# esp32comp.net
KiCad netlist of a schematic drawn in EAGLE
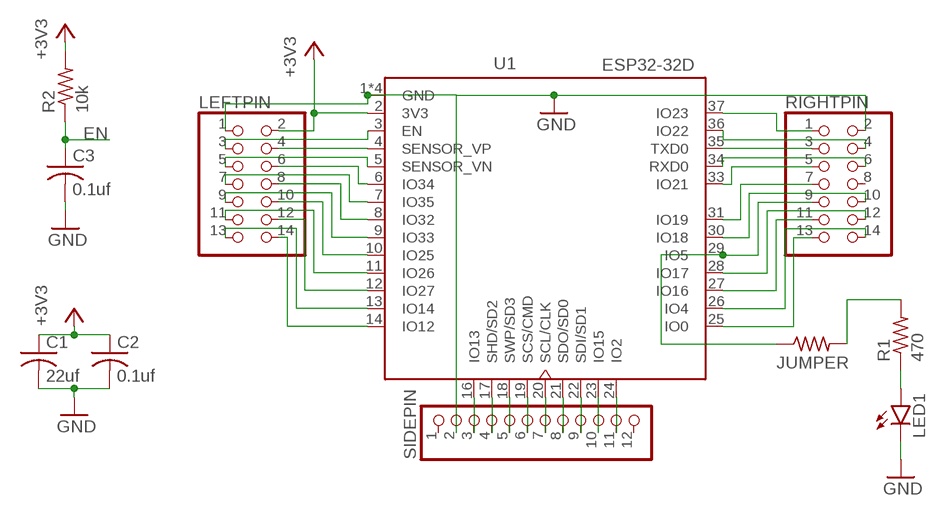
[diagram p0: schematic, sheet 1]

(export (version "E")
  (design (tool "Eeschema 10.0.6"))
  (components
    (comp (ref "C1")
      (value "22uf")
      (footprint "eagle-import:C1210")
      (libsource (lib "eagle-import") (part "C-USC1210"))
    )
    (comp (ref "C2")
      (value "0.1uf")
      (footprint "eagle-import:C0805")
      (libsource (lib "eagle-import") (part "C-USC0805"))
    )
    (comp (ref "C3")
      (value "0.1uf")
      (footprint "eagle-import:C0805")
      (libsource (lib "eagle-import") (part "C-USC0805"))
    )
    (comp (ref "JUMPER")
      (value "RC0603JR-070RL")
      (footprint "eagle-import:RES_0603")
      (fields
        (field (name "DIGIKEY_PART_NUMBER") "311-0.0GRTR-ND")
        (field (name "MANUFACTURER") "Yageo")
        (field (name "CREATED_BY") "PCBLayout.com")
      )
      (libsource (lib "eagle-import") (part "RC0603JR-070RL"))
    )
    (comp (ref "LED1")
      (value "LEDSML0805")
      (footprint "eagle-import:SML0805")
      (libsource (lib "eagle-import") (part "LEDSML0805"))
    )
    (comp (ref "LEFTPIN")
      (value "PINHD-2X7")
      (footprint "eagle-import:2X07")
      (libsource (lib "eagle-import") (part "PINHD-2X7"))
    )
    (comp (ref "R1")
      (value "470")
      (footprint "eagle-import:R0805")
      (libsource (lib "eagle-import") (part "R-US_R0805"))
    )
    (comp (ref "R2")
      (value "10k")
      (footprint "eagle-import:R0805")
      (libsource (lib "eagle-import") (part "R-US_R0805"))
    )
    (comp (ref "RIGHTPIN")
      (value "PINHD-2X7")
      (footprint "eagle-import:2X07")
      (libsource (lib "eagle-import") (part "PINHD-2X7"))
    )
    (comp (ref "SIDEPIN")
      (value "PINHD-1X12")
      (footprint "eagle-import:1X12")
      (libsource (lib "eagle-import") (part "PINHD-1X12"))
    )
    (comp (ref "U1")
      (value "ESP32-32D")
      (footprint "eagle-import:MODULE_ESP32-WROOM-32D")
      (fields (field (name "MF") "Espressif Systems") (field (name "MP") "ESP32-WROOM-32D"))
      (libsource (lib "eagle-import") (part "ESP32-32D"))
    )
  )
  (nets
    (net (code "1") (name "+3V3") (class "Default")
      (node (ref "C1") (pin "1") (pinfunction "1_1") (pintype "passive"))
      (node (ref "C2") (pin "1") (pinfunction "1_1") (pintype "passive"))
      (node (ref "LEFTPIN") (pin "2") (pinfunction "2_2") (pintype "passive"))
      (node (ref "R2") (pin "2") (pinfunction "2_2") (pintype "passive"))
      (node (ref "U1") (pin "2") (pinfunction "3V3_2") (pintype "power_in"))
    )
    (net (code "2") (name "/EN") (class "Default")
      (node (ref "C3") (pin "1") (pinfunction "1_1") (pintype "passive"))
      (node (ref "LEFTPIN") (pin "3") (pinfunction "3_3") (pintype "passive"))
      (node (ref "R2") (pin "1") (pinfunction "1_1") (pintype "passive"))
      (node (ref "U1") (pin "3") (pinfunction "EN_3") (pintype "input"))
    )
    (net (code "3") (name "GND") (class "Default")
      (node (ref "C1") (pin "2") (pinfunction "2_2") (pintype "passive"))
      (node (ref "C2") (pin "2") (pinfunction "2_2") (pintype "passive"))
      (node (ref "C3") (pin "2") (pinfunction "2_2") (pintype "passive"))
      (node (ref "LED1") (pin "C") (pinfunction "C_C") (pintype "passive"))
      (node (ref "LEFTPIN") (pin "1") (pinfunction "1_1") (pintype "passive"))
      (node (ref "RIGHTPIN") (pin "2") (pinfunction "2_2") (pintype "passive"))
      (node (ref "SIDEPIN") (pin "2") (pinfunction "2_2") (pintype "passive"))
      (node (ref "U1") (pin "1") (pinfunction "GND_1") (pintype "power_in"))
      (node (ref "U1") (pin "15") (pinfunction "GND_15") (pintype "power_in"))
      (node (ref "U1") (pin "38") (pinfunction "GND_38") (pintype "power_in"))
      (node (ref "U1") (pin "39") (pinfunction "GND_39") (pintype "power_in"))
    )
    (net (code "4") (name "Net-(JUMPER-Pad2)") (class "Default")
      (node (ref "JUMPER") (pin "2") (pinfunction "2_2") (pintype "passive"))
      (node (ref "R1") (pin "2") (pinfunction "2_2") (pintype "passive"))
    )
    (net (code "5") (name "Net-(LED1-PadA)") (class "Default")
      (node (ref "LED1") (pin "A") (pinfunction "A_A") (pintype "passive"))
      (node (ref "R1") (pin "1") (pinfunction "1_1") (pintype "passive"))
    )
    (net (code "6") (name "Net-(U1-IO0)") (class "Default")
      (node (ref "RIGHTPIN") (pin "13") (pinfunction "13_13") (pintype "passive"))
      (node (ref "U1") (pin "25") (pinfunction "IO0_25") (pintype "bidirectional"))
    )
    (net (code "7") (name "Net-(U1-IO2)") (class "Default")
      (node (ref "SIDEPIN") (pin "11") (pinfunction "11_11") (pintype "passive"))
      (node (ref "U1") (pin "24") (pinfunction "IO2_24") (pintype "bidirectional"))
    )
    (net (code "8") (name "Net-(U1-IO4)") (class "Default")
      (node (ref "RIGHTPIN") (pin "14") (pinfunction "14_14") (pintype "passive"))
      (node (ref "U1") (pin "26") (pinfunction "IO4_26") (pintype "bidirectional"))
    )
    (net (code "9") (name "Net-(U1-IO5)") (class "Default")
      (node (ref "JUMPER") (pin "1") (pinfunction "1_1") (pintype "passive"))
      (node (ref "RIGHTPIN") (pin "9") (pinfunction "9_9") (pintype "passive"))
      (node (ref "U1") (pin "29") (pinfunction "IO5_29") (pintype "bidirectional"))
    )
    (net (code "10") (name "Net-(U1-IO12)") (class "Default")
      (node (ref "LEFTPIN") (pin "14") (pinfunction "14_14") (pintype "passive"))
      (node (ref "U1") (pin "14") (pinfunction "IO12_14") (pintype "bidirectional"))
    )
    (net (code "11") (name "Net-(U1-IO13)") (class "Default")
      (node (ref "SIDEPIN") (pin "3") (pinfunction "3_3") (pintype "passive"))
      (node (ref "U1") (pin "16") (pinfunction "IO13_16") (pintype "bidirectional"))
    )
    (net (code "12") (name "Net-(U1-IO14)") (class "Default")
      (node (ref "LEFTPIN") (pin "13") (pinfunction "13_13") (pintype "passive"))
      (node (ref "U1") (pin "13") (pinfunction "IO14_13") (pintype "bidirectional"))
    )
    (net (code "13") (name "Net-(U1-IO15)") (class "Default")
      (node (ref "SIDEPIN") (pin "10") (pinfunction "10_10") (pintype "passive"))
      (node (ref "U1") (pin "23") (pinfunction "IO15_23") (pintype "bidirectional"))
    )
    (net (code "14") (name "Net-(U1-IO16)") (class "Default")
      (node (ref "RIGHTPIN") (pin "11") (pinfunction "11_11") (pintype "passive"))
      (node (ref "U1") (pin "27") (pinfunction "IO16_27") (pintype "bidirectional"))
    )
    (net (code "15") (name "Net-(U1-IO17)") (class "Default")
      (node (ref "RIGHTPIN") (pin "12") (pinfunction "12_12") (pintype "passive"))
      (node (ref "U1") (pin "28") (pinfunction "IO17_28") (pintype "bidirectional"))
    )
    (net (code "16") (name "Net-(U1-IO18)") (class "Default")
      (node (ref "RIGHTPIN") (pin "10") (pinfunction "10_10") (pintype "passive"))
      (node (ref "U1") (pin "30") (pinfunction "IO18_30") (pintype "bidirectional"))
    )
    (net (code "17") (name "Net-(U1-IO19)") (class "Default")
      (node (ref "RIGHTPIN") (pin "7") (pinfunction "7_7") (pintype "passive"))
      (node (ref "U1") (pin "31") (pinfunction "IO19_31") (pintype "bidirectional"))
    )
    (net (code "18") (name "Net-(U1-IO21)") (class "Default")
      (node (ref "RIGHTPIN") (pin "5") (pinfunction "5_5") (pintype "passive"))
      (node (ref "U1") (pin "33") (pinfunction "IO21_33") (pintype "bidirectional"))
    )
    (net (code "19") (name "Net-(U1-IO22)") (class "Default")
      (node (ref "RIGHTPIN") (pin "4") (pinfunction "4_4") (pintype "passive"))
      (node (ref "U1") (pin "36") (pinfunction "IO22_36") (pintype "bidirectional"))
    )
    (net (code "20") (name "Net-(U1-IO23)") (class "Default")
      (node (ref "RIGHTPIN") (pin "1") (pinfunction "1_1") (pintype "passive"))
      (node (ref "U1") (pin "37") (pinfunction "IO23_37") (pintype "bidirectional"))
    )
    (net (code "21") (name "Net-(U1-IO25)") (class "Default")
      (node (ref "LEFTPIN") (pin "10") (pinfunction "10_10") (pintype "passive"))
      (node (ref "U1") (pin "10") (pinfunction "IO25_10") (pintype "bidirectional"))
    )
    (net (code "22") (name "Net-(U1-IO26)") (class "Default")
      (node (ref "LEFTPIN") (pin "11") (pinfunction "11_11") (pintype "passive"))
      (node (ref "U1") (pin "11") (pinfunction "IO26_11") (pintype "bidirectional"))
    )
    (net (code "23") (name "Net-(U1-IO27)") (class "Default")
      (node (ref "LEFTPIN") (pin "12") (pinfunction "12_12") (pintype "passive"))
      (node (ref "U1") (pin "12") (pinfunction "IO27_12") (pintype "bidirectional"))
    )
    (net (code "24") (name "Net-(U1-IO32)") (class "Default")
      (node (ref "LEFTPIN") (pin "8") (pinfunction "8_8") (pintype "passive"))
      (node (ref "U1") (pin "8") (pinfunction "IO32_8") (pintype "bidirectional"))
    )
    (net (code "25") (name "Net-(U1-IO33)") (class "Default")
      (node (ref "LEFTPIN") (pin "9") (pinfunction "9_9") (pintype "passive"))
      (node (ref "U1") (pin "9") (pinfunction "IO33_9") (pintype "bidirectional"))
    )
    (net (code "26") (name "Net-(U1-IO34)") (class "Default")
      (node (ref "LEFTPIN") (pin "6") (pinfunction "6_6") (pintype "passive"))
      (node (ref "U1") (pin "6") (pinfunction "IO34_6") (pintype "bidirectional"))
    )
    (net (code "27") (name "Net-(U1-IO35)") (class "Default")
      (node (ref "LEFTPIN") (pin "7") (pinfunction "7_7") (pintype "passive"))
      (node (ref "U1") (pin "7") (pinfunction "IO35_7") (pintype "bidirectional"))
    )
    (net (code "28") (name "Net-(U1-RXD0)") (class "Default")
      (node (ref "RIGHTPIN") (pin "6") (pinfunction "6_6") (pintype "passive"))
      (node (ref "U1") (pin "34") (pinfunction "RXD0_34") (pintype "bidirectional"))
    )
    (net (code "29") (name "Net-(U1-SCL{slash}CLK)") (class "Default")
      (node (ref "SIDEPIN") (pin "7") (pinfunction "7_7") (pintype "passive"))
      (node (ref "U1") (pin "20") (pinfunction "SCL/CLK_20") (pintype "bidirectional"))
    )
    (net (code "30") (name "Net-(U1-SCS{slash}CMD)") (class "Default")
      (node (ref "SIDEPIN") (pin "6") (pinfunction "6_6") (pintype "passive"))
      (node (ref "U1") (pin "19") (pinfunction "SCS/CMD_19") (pintype "bidirectional"))
    )
    (net (code "31") (name "Net-(U1-SDI{slash}SD1)") (class "Default")
      (node (ref "SIDEPIN") (pin "9") (pinfunction "9_9") (pintype "passive"))
      (node (ref "U1") (pin "22") (pinfunction "SDI/SD1_22") (pintype "bidirectional"))
    )
    (net (code "32") (name "Net-(U1-SDO{slash}SD0)") (class "Default")
      (node (ref "SIDEPIN") (pin "8") (pinfunction "8_8") (pintype "passive"))
      (node (ref "U1") (pin "21") (pinfunction "SDO/SD0_21") (pintype "bidirectional"))
    )
    (net (code "33") (name "Net-(U1-SENSOR_VN)") (class "Default")
      (node (ref "LEFTPIN") (pin "5") (pinfunction "5_5") (pintype "passive"))
      (node (ref "U1") (pin "5") (pinfunction "SENSOR_VN_5") (pintype "input"))
    )
    (net (code "34") (name "Net-(U1-SENSOR_VP)") (class "Default")
      (node (ref "LEFTPIN") (pin "4") (pinfunction "4_4") (pintype "passive"))
      (node (ref "U1") (pin "4") (pinfunction "SENSOR_VP_4") (pintype "input"))
    )
    (net (code "35") (name "Net-(U1-SHD{slash}SD2)") (class "Default")
      (node (ref "SIDEPIN") (pin "4") (pinfunction "4_4") (pintype "passive"))
      (node (ref "U1") (pin "17") (pinfunction "SHD/SD2_17") (pintype "bidirectional"))
    )
    (net (code "36") (name "Net-(U1-SWP{slash}SD3)") (class "Default")
      (node (ref "SIDEPIN") (pin "5") (pinfunction "5_5") (pintype "passive"))
      (node (ref "U1") (pin "18") (pinfunction "SWP/SD3_18") (pintype "bidirectional"))
    )
    (net (code "37") (name "Net-(U1-TXD0)") (class "Default")
      (node (ref "RIGHTPIN") (pin "3") (pinfunction "3_3") (pintype "passive"))
      (node (ref "U1") (pin "35") (pinfunction "TXD0_35") (pintype "bidirectional"))
    )
    (net (code "38") (name "unconnected-(RIGHTPIN-Pad8)") (class "Default")
      (node (ref "RIGHTPIN") (pin "8") (pinfunction "8_8") (pintype "passive"))
    )
    (net (code "39") (name "unconnected-(SIDEPIN-Pad1)") (class "Default")
      (node (ref "SIDEPIN") (pin "1") (pinfunction "1_1") (pintype "passive"))
    )
    (net (code "40") (name "unconnected-(SIDEPIN-Pad12)") (class "Default")
      (node (ref "SIDEPIN") (pin "12") (pinfunction "12_12") (pintype "passive"))
    )
  )
)
